# SWITCHCONTROL.net
KiCad netlist of a schematic drawn in EAGLE
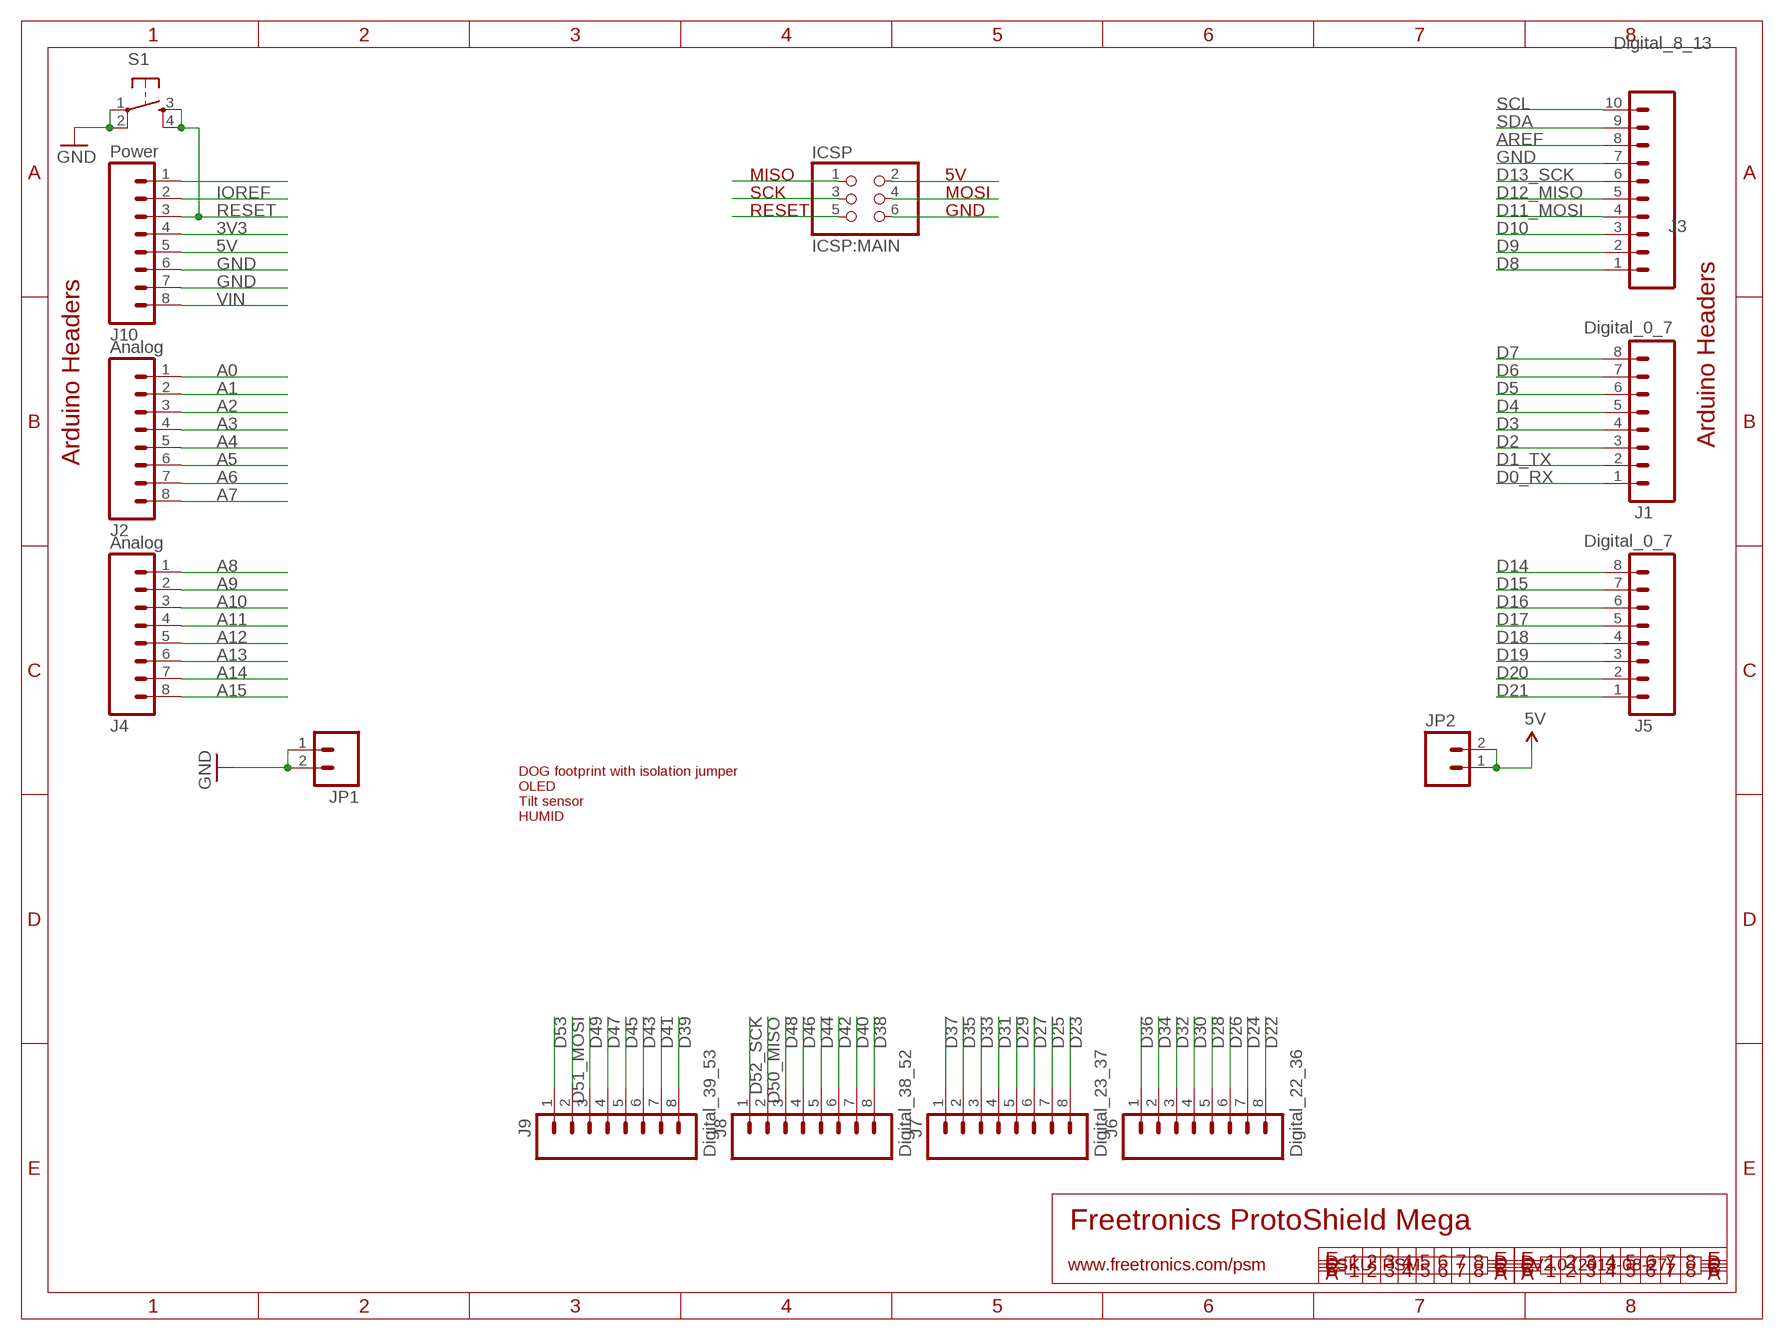
[diagram p0: schematic, sheet 1]
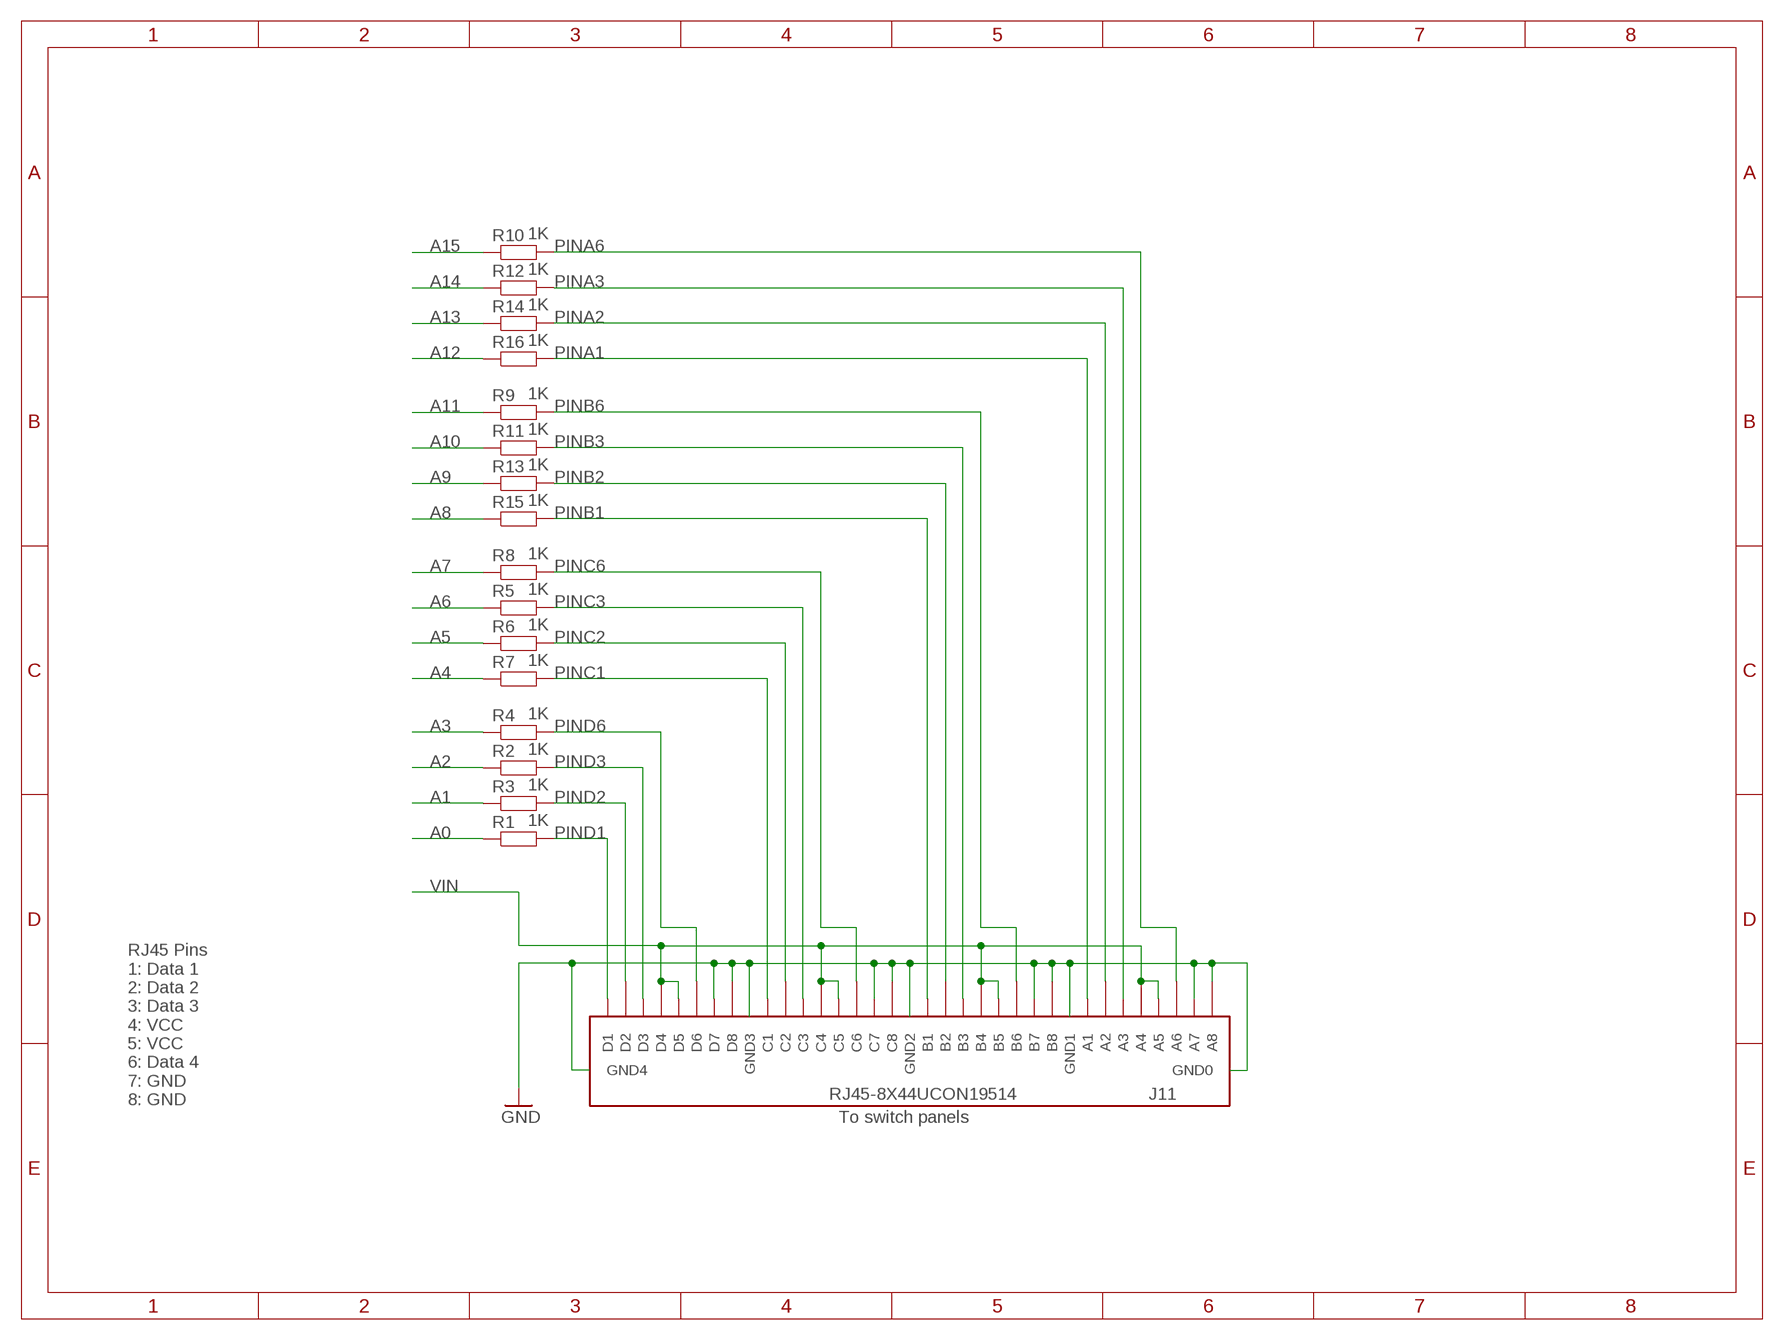
[diagram p1: schematic, sheet 2]
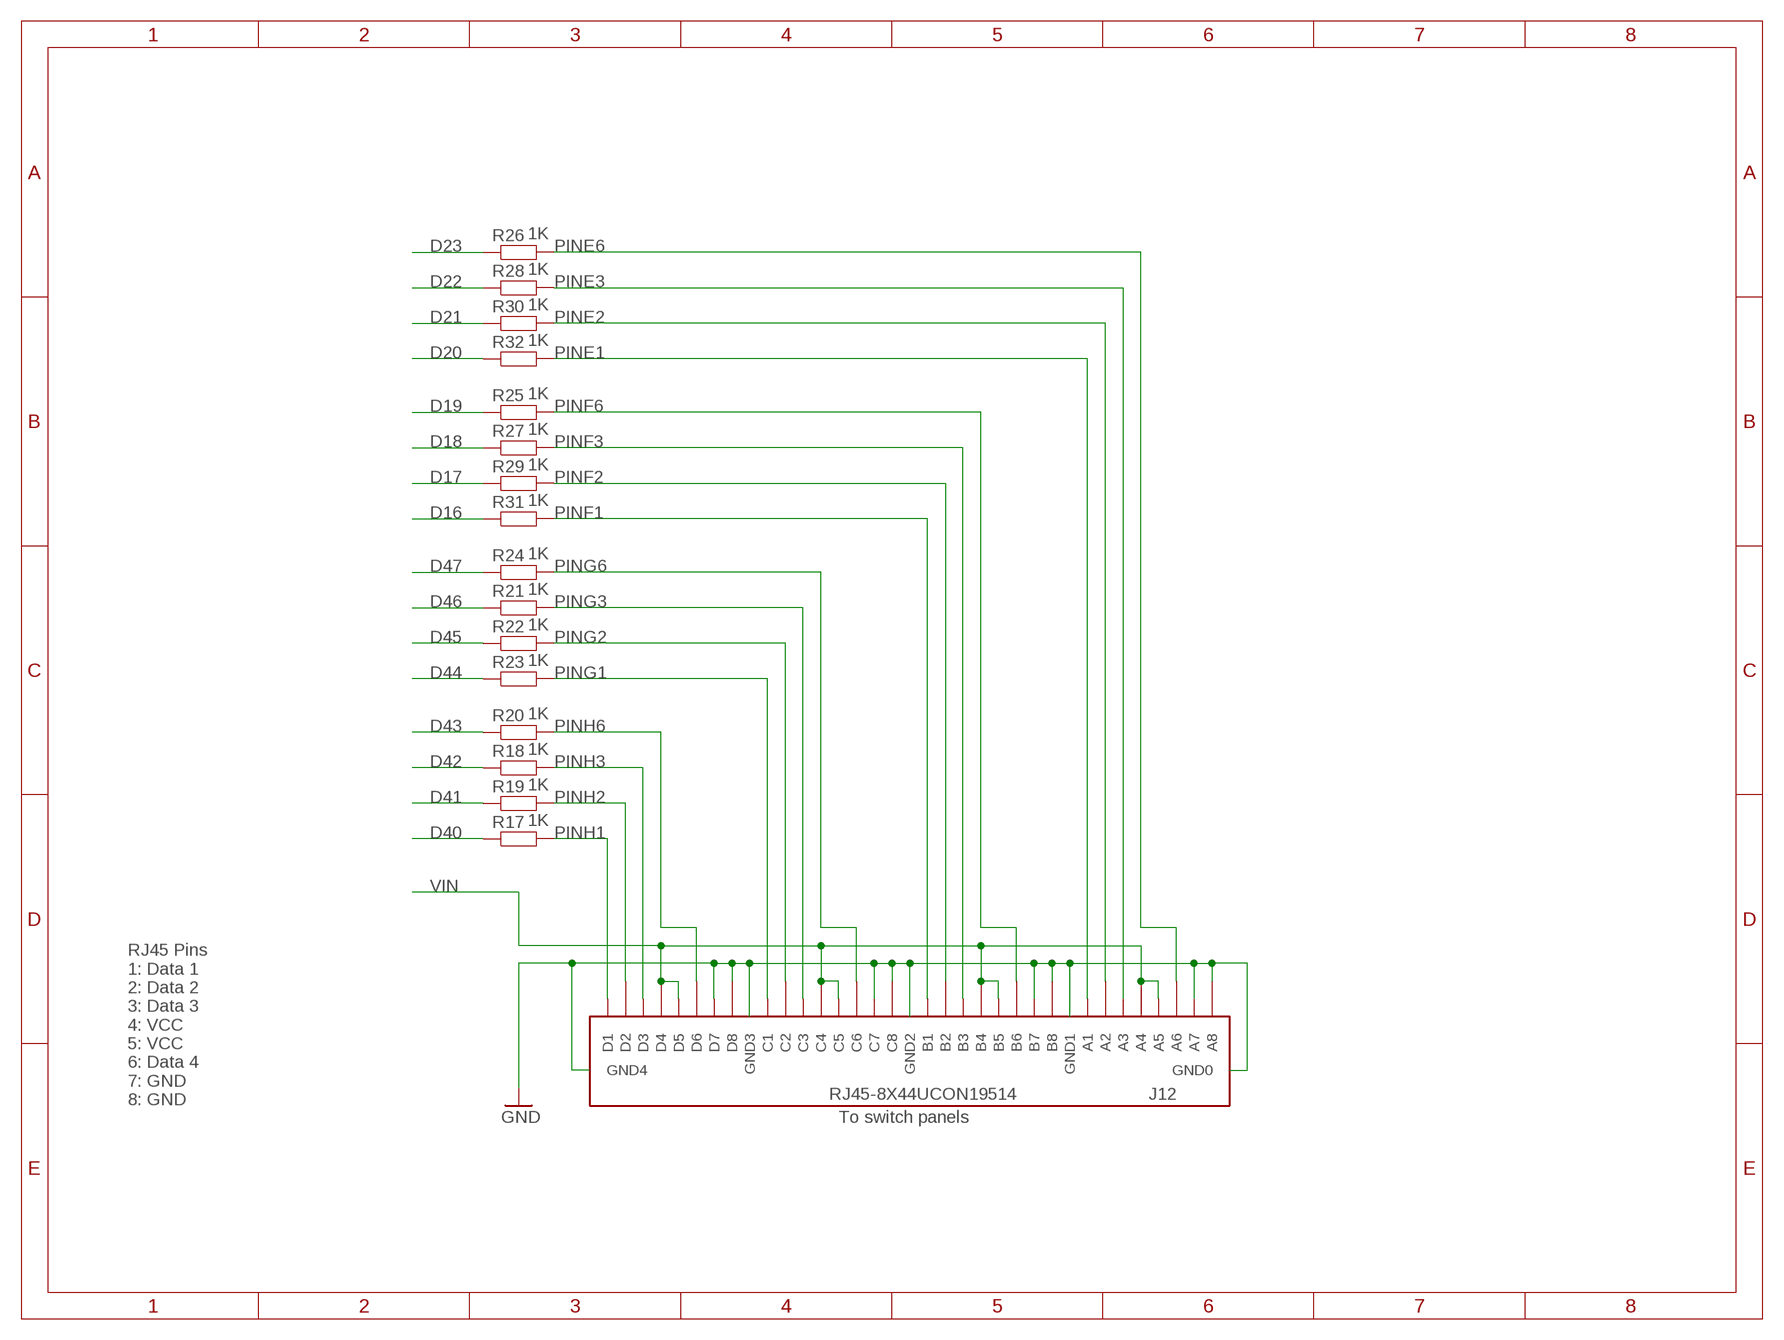
[diagram p2: schematic, sheet 3]
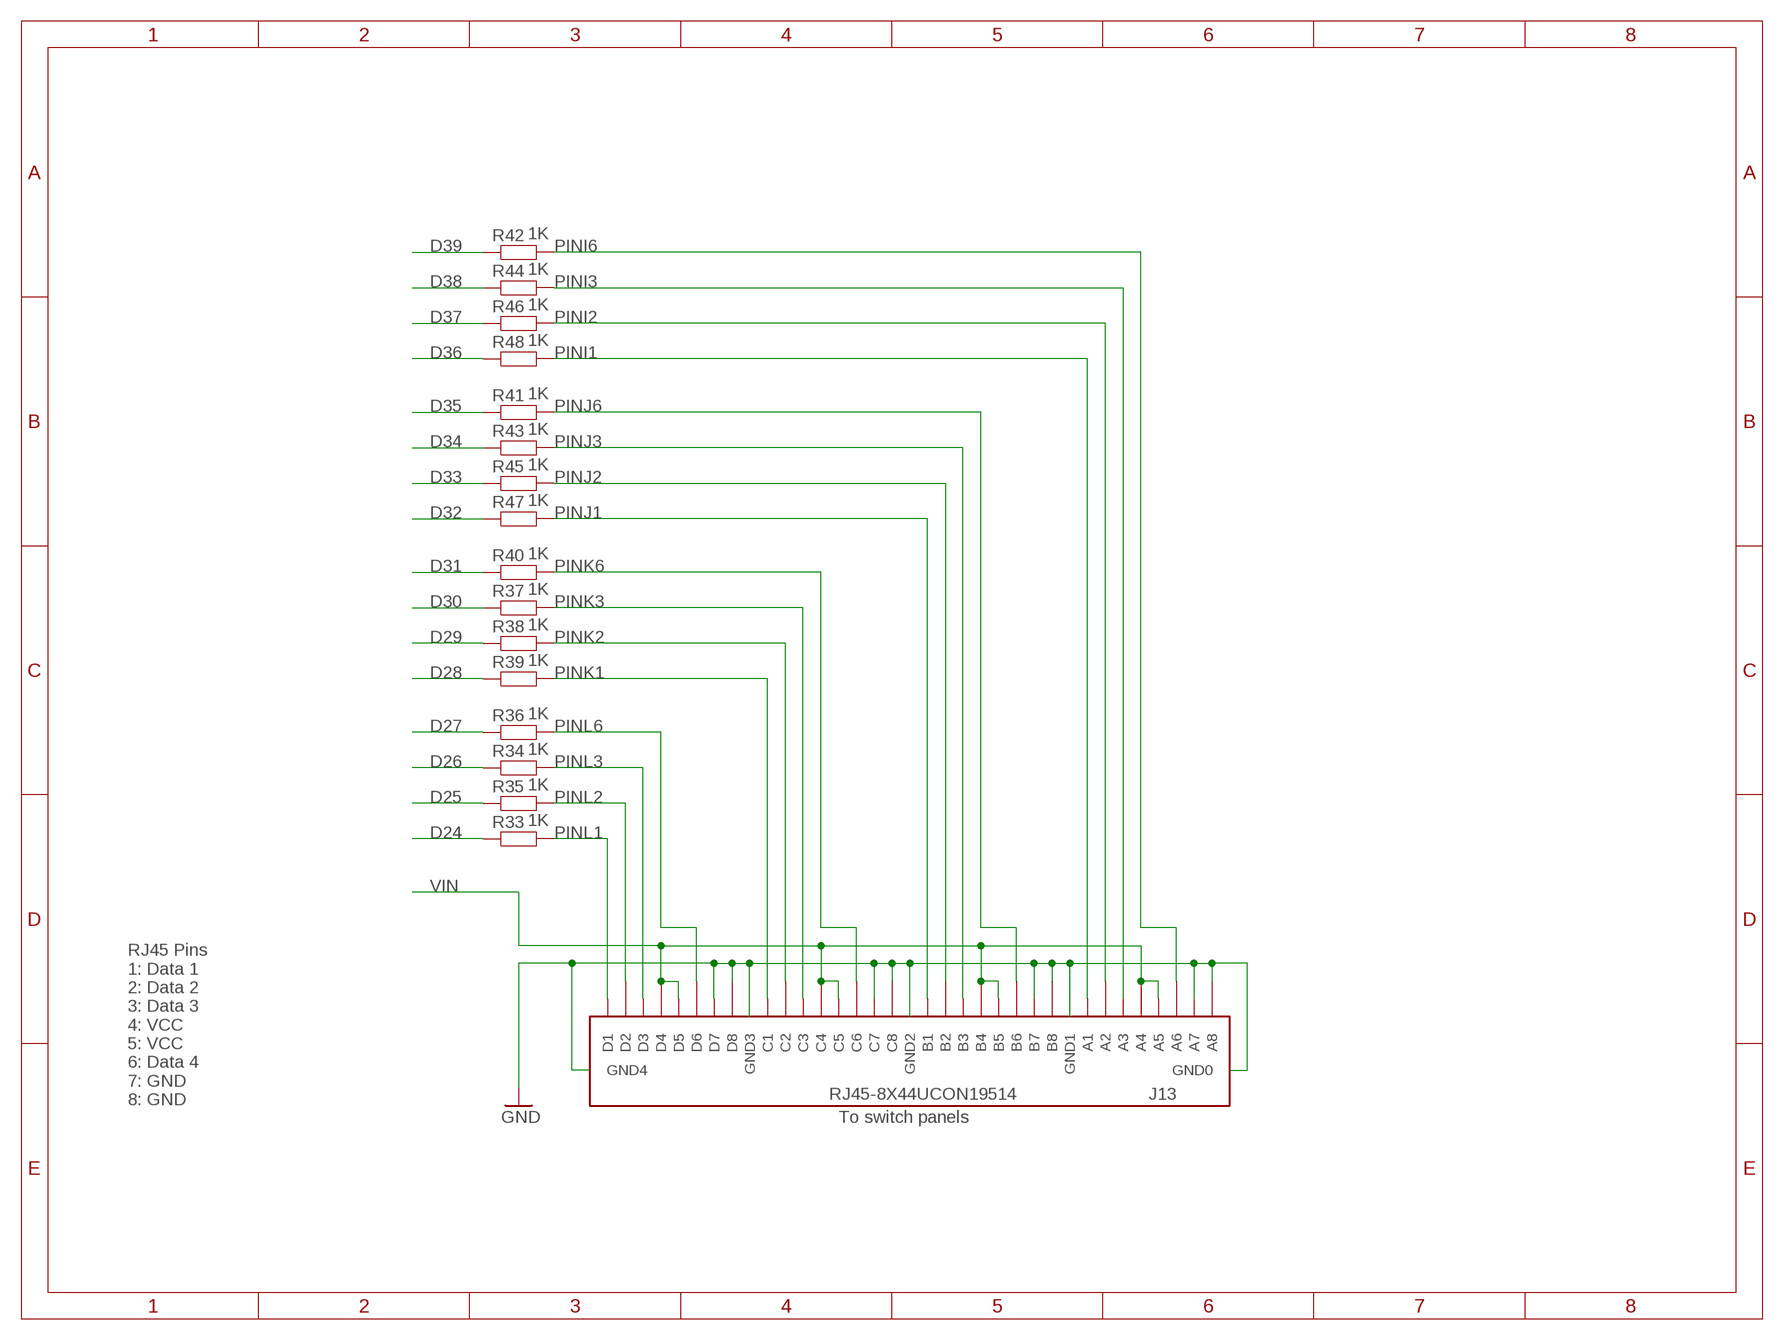
[diagram p3: schematic, sheet 4]

(export (version "E")
  (design (tool "Eeschema 10.0.6"))
  (components
    (comp (ref "J13")
      (value "RJ45-8X44UCON19514")
      (footprint "eagle-import:RJ45-8X4")
      (libsource (lib "eagle-import") (part "RJ45-8X44UCON19514"))
    )
    (comp (ref "R33")
      (value "1K")
      (footprint "eagle-import:0603")
      (libsource (lib "eagle-import") (part "RESISTOR0603"))
    )
    (comp (ref "R34")
      (value "1K")
      (footprint "eagle-import:0603")
      (libsource (lib "eagle-import") (part "RESISTOR0603"))
    )
    (comp (ref "R35")
      (value "1K")
      (footprint "eagle-import:0603")
      (libsource (lib "eagle-import") (part "RESISTOR0603"))
    )
    (comp (ref "R36")
      (value "1K")
      (footprint "eagle-import:0603")
      (libsource (lib "eagle-import") (part "RESISTOR0603"))
    )
    (comp (ref "R37")
      (value "1K")
      (footprint "eagle-import:0603")
      (libsource (lib "eagle-import") (part "RESISTOR0603"))
    )
    (comp (ref "R38")
      (value "1K")
      (footprint "eagle-import:0603")
      (libsource (lib "eagle-import") (part "RESISTOR0603"))
    )
    (comp (ref "R39")
      (value "1K")
      (footprint "eagle-import:0603")
      (libsource (lib "eagle-import") (part "RESISTOR0603"))
    )
    (comp (ref "R40")
      (value "1K")
      (footprint "eagle-import:0603")
      (libsource (lib "eagle-import") (part "RESISTOR0603"))
    )
    (comp (ref "R41")
      (value "1K")
      (footprint "eagle-import:0603")
      (libsource (lib "eagle-import") (part "RESISTOR0603"))
    )
    (comp (ref "R42")
      (value "1K")
      (footprint "eagle-import:0603")
      (libsource (lib "eagle-import") (part "RESISTOR0603"))
    )
    (comp (ref "R43")
      (value "1K")
      (footprint "eagle-import:0603")
      (libsource (lib "eagle-import") (part "RESISTOR0603"))
    )
    (comp (ref "R44")
      (value "1K")
      (footprint "eagle-import:0603")
      (libsource (lib "eagle-import") (part "RESISTOR0603"))
    )
    (comp (ref "R45")
      (value "1K")
      (footprint "eagle-import:0603")
      (libsource (lib "eagle-import") (part "RESISTOR0603"))
    )
    (comp (ref "R46")
      (value "1K")
      (footprint "eagle-import:0603")
      (libsource (lib "eagle-import") (part "RESISTOR0603"))
    )
    (comp (ref "R47")
      (value "1K")
      (footprint "eagle-import:0603")
      (libsource (lib "eagle-import") (part "RESISTOR0603"))
    )
    (comp (ref "R48")
      (value "1K")
      (footprint "eagle-import:0603")
      (libsource (lib "eagle-import") (part "RESISTOR0603"))
    )
    (comp (ref "J12")
      (value "RJ45-8X44UCON19514")
      (footprint "eagle-import:RJ45-8X4")
      (libsource (lib "eagle-import") (part "RJ45-8X44UCON19514"))
    )
    (comp (ref "R17")
      (value "1K")
      (footprint "eagle-import:0603")
      (libsource (lib "eagle-import") (part "RESISTOR0603"))
    )
    (comp (ref "R18")
      (value "1K")
      (footprint "eagle-import:0603")
      (libsource (lib "eagle-import") (part "RESISTOR0603"))
    )
    (comp (ref "R19")
      (value "1K")
      (footprint "eagle-import:0603")
      (libsource (lib "eagle-import") (part "RESISTOR0603"))
    )
    (comp (ref "R20")
      (value "1K")
      (footprint "eagle-import:0603")
      (libsource (lib "eagle-import") (part "RESISTOR0603"))
    )
    (comp (ref "R21")
      (value "1K")
      (footprint "eagle-import:0603")
      (libsource (lib "eagle-import") (part "RESISTOR0603"))
    )
    (comp (ref "R22")
      (value "1K")
      (footprint "eagle-import:0603")
      (libsource (lib "eagle-import") (part "RESISTOR0603"))
    )
    (comp (ref "R23")
      (value "1K")
      (footprint "eagle-import:0603")
      (libsource (lib "eagle-import") (part "RESISTOR0603"))
    )
    (comp (ref "R24")
      (value "1K")
      (footprint "eagle-import:0603")
      (libsource (lib "eagle-import") (part "RESISTOR0603"))
    )
    (comp (ref "R25")
      (value "1K")
      (footprint "eagle-import:0603")
      (libsource (lib "eagle-import") (part "RESISTOR0603"))
    )
    (comp (ref "R26")
      (value "1K")
      (footprint "eagle-import:0603")
      (libsource (lib "eagle-import") (part "RESISTOR0603"))
    )
    (comp (ref "R27")
      (value "1K")
      (footprint "eagle-import:0603")
      (libsource (lib "eagle-import") (part "RESISTOR0603"))
    )
    (comp (ref "R28")
      (value "1K")
      (footprint "eagle-import:0603")
      (libsource (lib "eagle-import") (part "RESISTOR0603"))
    )
    (comp (ref "R29")
      (value "1K")
      (footprint "eagle-import:0603")
      (libsource (lib "eagle-import") (part "RESISTOR0603"))
    )
    (comp (ref "R30")
      (value "1K")
      (footprint "eagle-import:0603")
      (libsource (lib "eagle-import") (part "RESISTOR0603"))
    )
    (comp (ref "R31")
      (value "1K")
      (footprint "eagle-import:0603")
      (libsource (lib "eagle-import") (part "RESISTOR0603"))
    )
    (comp (ref "R32")
      (value "1K")
      (footprint "eagle-import:0603")
      (libsource (lib "eagle-import") (part "RESISTOR0603"))
    )
    (comp (ref "J11")
      (value "RJ45-8X44UCON19514")
      (footprint "eagle-import:RJ45-8X4")
      (libsource (lib "eagle-import") (part "RJ45-8X44UCON19514"))
    )
    (comp (ref "R1")
      (value "1K")
      (footprint "eagle-import:0603")
      (libsource (lib "eagle-import") (part "RESISTOR0603"))
    )
    (comp (ref "R2")
      (value "1K")
      (footprint "eagle-import:0603")
      (libsource (lib "eagle-import") (part "RESISTOR0603"))
    )
    (comp (ref "R3")
      (value "1K")
      (footprint "eagle-import:0603")
      (libsource (lib "eagle-import") (part "RESISTOR0603"))
    )
    (comp (ref "R4")
      (value "1K")
      (footprint "eagle-import:0603")
      (libsource (lib "eagle-import") (part "RESISTOR0603"))
    )
    (comp (ref "R5")
      (value "1K")
      (footprint "eagle-import:0603")
      (libsource (lib "eagle-import") (part "RESISTOR0603"))
    )
    (comp (ref "R6")
      (value "1K")
      (footprint "eagle-import:0603")
      (libsource (lib "eagle-import") (part "RESISTOR0603"))
    )
    (comp (ref "R7")
      (value "1K")
      (footprint "eagle-import:0603")
      (libsource (lib "eagle-import") (part "RESISTOR0603"))
    )
    (comp (ref "R8")
      (value "1K")
      (footprint "eagle-import:0603")
      (libsource (lib "eagle-import") (part "RESISTOR0603"))
    )
    (comp (ref "R9")
      (value "1K")
      (footprint "eagle-import:0603")
      (libsource (lib "eagle-import") (part "RESISTOR0603"))
    )
    (comp (ref "R10")
      (value "1K")
      (footprint "eagle-import:0603")
      (libsource (lib "eagle-import") (part "RESISTOR0603"))
    )
    (comp (ref "R11")
      (value "1K")
      (footprint "eagle-import:0603")
      (libsource (lib "eagle-import") (part "RESISTOR0603"))
    )
    (comp (ref "R12")
      (value "1K")
      (footprint "eagle-import:0603")
      (libsource (lib "eagle-import") (part "RESISTOR0603"))
    )
    (comp (ref "R13")
      (value "1K")
      (footprint "eagle-import:0603")
      (libsource (lib "eagle-import") (part "RESISTOR0603"))
    )
    (comp (ref "R14")
      (value "1K")
      (footprint "eagle-import:0603")
      (libsource (lib "eagle-import") (part "RESISTOR0603"))
    )
    (comp (ref "R15")
      (value "1K")
      (footprint "eagle-import:0603")
      (libsource (lib "eagle-import") (part "RESISTOR0603"))
    )
    (comp (ref "R16")
      (value "1K")
      (footprint "eagle-import:0603")
      (libsource (lib "eagle-import") (part "RESISTOR0603"))
    )
    (comp (ref "ICSP")
      (value "ICSP:MAIN")
      (footprint "eagle-import:2X03")
      (libsource (lib "eagle-import") (part "PINHD-2X3"))
    )
    (comp (ref "J1")
      (value "Digital_0_7")
      (footprint "eagle-import:1X08")
      (libsource (lib "eagle-import") (part "M08"))
    )
    (comp (ref "J2")
      (value "Analog")
      (footprint "eagle-import:1X08")
      (libsource (lib "eagle-import") (part "freetronics-master-v1_M08"))
    )
    (comp (ref "J3")
      (value "Digital_8_13")
      (footprint "eagle-import:1X10")
      (libsource (lib "eagle-import") (part "M100.1"))
    )
    (comp (ref "J4")
      (value "Analog")
      (footprint "eagle-import:1X08")
      (libsource (lib "eagle-import") (part "freetronics-master-v1_M08"))
    )
    (comp (ref "J5")
      (value "Digital_0_7")
      (footprint "eagle-import:1X08")
      (libsource (lib "eagle-import") (part "M08"))
    )
    (comp (ref "J6")
      (value "Digital_22_36")
      (footprint "eagle-import:1X08")
      (libsource (lib "eagle-import") (part "M08"))
    )
    (comp (ref "J7")
      (value "Digital_23_37")
      (footprint "eagle-import:1X08")
      (libsource (lib "eagle-import") (part "M08"))
    )
    (comp (ref "J8")
      (value "Digital_38_52")
      (footprint "eagle-import:1X08")
      (libsource (lib "eagle-import") (part "M08"))
    )
    (comp (ref "J9")
      (value "Digital_39_53")
      (footprint "eagle-import:1X08")
      (libsource (lib "eagle-import") (part "M08"))
    )
    (comp (ref "J10")
      (value "Power")
      (footprint "eagle-import:1X08")
      (libsource (lib "eagle-import") (part "freetronics-master-v1_M08"))
    )
    (comp (ref "JP1")
      (value "M02PTH")
      (footprint "eagle-import:1X02")
      (libsource (lib "eagle-import") (part "M02PTH"))
    )
    (comp (ref "JP2")
      (value "M02PTH")
      (footprint "eagle-import:1X02")
      (libsource (lib "eagle-import") (part "M02PTH"))
    )
    (comp (ref "S1")
      (value "TAC_SWITCHPTH")
      (footprint "eagle-import:TACTILE-PTH")
      (libsource (lib "eagle-import") (part "TAC_SWITCHPTH"))
    )
  )
  (nets
    (net (code "1") (name "3V3") (class "Default")
      (node (ref "J10") (pin "4") (pinfunction "4_4") (pintype "passive"))
    )
    (net (code "2") (name "5V") (class "Default")
      (node (ref "J10") (pin "5") (pinfunction "5_5") (pintype "passive"))
      (node (ref "JP2") (pin "1") (pinfunction "1_1") (pintype "passive"))
      (node (ref "JP2") (pin "2") (pinfunction "2_2") (pintype "passive"))
    )
    (net (code "3") (name "A0") (class "Default")
      (node (ref "J2") (pin "1") (pinfunction "1_1") (pintype "passive"))
      (node (ref "R1") (pin "1") (pinfunction "1_1") (pintype "passive"))
    )
    (net (code "4") (name "A1") (class "Default")
      (node (ref "J2") (pin "2") (pinfunction "2_2") (pintype "passive"))
      (node (ref "R3") (pin "1") (pinfunction "1_1") (pintype "passive"))
    )
    (net (code "5") (name "A2") (class "Default")
      (node (ref "J2") (pin "3") (pinfunction "3_3") (pintype "passive"))
      (node (ref "R2") (pin "1") (pinfunction "1_1") (pintype "passive"))
    )
    (net (code "6") (name "A3") (class "Default")
      (node (ref "J2") (pin "4") (pinfunction "4_4") (pintype "passive"))
      (node (ref "R4") (pin "1") (pinfunction "1_1") (pintype "passive"))
    )
    (net (code "7") (name "A4") (class "Default")
      (node (ref "J2") (pin "5") (pinfunction "5_5") (pintype "passive"))
      (node (ref "R7") (pin "1") (pinfunction "1_1") (pintype "passive"))
    )
    (net (code "8") (name "A5") (class "Default")
      (node (ref "J2") (pin "6") (pinfunction "6_6") (pintype "passive"))
      (node (ref "R6") (pin "1") (pinfunction "1_1") (pintype "passive"))
    )
    (net (code "9") (name "A6") (class "Default")
      (node (ref "J2") (pin "7") (pinfunction "7_7") (pintype "passive"))
      (node (ref "R5") (pin "1") (pinfunction "1_1") (pintype "passive"))
    )
    (net (code "10") (name "A7") (class "Default")
      (node (ref "J2") (pin "8") (pinfunction "8_8") (pintype "passive"))
      (node (ref "R8") (pin "1") (pinfunction "1_1") (pintype "passive"))
    )
    (net (code "11") (name "A8") (class "Default")
      (node (ref "J4") (pin "1") (pinfunction "1_1") (pintype "passive"))
      (node (ref "R15") (pin "1") (pinfunction "1_1") (pintype "passive"))
    )
    (net (code "12") (name "A9") (class "Default")
      (node (ref "J4") (pin "2") (pinfunction "2_2") (pintype "passive"))
      (node (ref "R13") (pin "1") (pinfunction "1_1") (pintype "passive"))
    )
    (net (code "13") (name "A10") (class "Default")
      (node (ref "J4") (pin "3") (pinfunction "3_3") (pintype "passive"))
      (node (ref "R11") (pin "1") (pinfunction "1_1") (pintype "passive"))
    )
    (net (code "14") (name "A11") (class "Default")
      (node (ref "J4") (pin "4") (pinfunction "4_4") (pintype "passive"))
      (node (ref "R9") (pin "1") (pinfunction "1_1") (pintype "passive"))
    )
    (net (code "15") (name "A12") (class "Default")
      (node (ref "J4") (pin "5") (pinfunction "5_5") (pintype "passive"))
      (node (ref "R16") (pin "1") (pinfunction "1_1") (pintype "passive"))
    )
    (net (code "16") (name "A13") (class "Default")
      (node (ref "J4") (pin "6") (pinfunction "6_6") (pintype "passive"))
      (node (ref "R14") (pin "1") (pinfunction "1_1") (pintype "passive"))
    )
    (net (code "17") (name "A14") (class "Default")
      (node (ref "J4") (pin "7") (pinfunction "7_7") (pintype "passive"))
      (node (ref "R12") (pin "1") (pinfunction "1_1") (pintype "passive"))
    )
    (net (code "18") (name "A15") (class "Default")
      (node (ref "J4") (pin "8") (pinfunction "8_8") (pintype "passive"))
      (node (ref "R10") (pin "1") (pinfunction "1_1") (pintype "passive"))
    )
    (net (code "19") (name "AREF") (class "Default")
      (node (ref "J3") (pin "8") (pinfunction "8_8") (pintype "passive"))
    )
    (net (code "20") (name "D0_RX") (class "Default")
      (node (ref "J1") (pin "1") (pinfunction "1_1") (pintype "passive"))
    )
    (net (code "21") (name "D1_TX") (class "Default")
      (node (ref "J1") (pin "2") (pinfunction "2_2") (pintype "passive"))
    )
    (net (code "22") (name "D2") (class "Default")
      (node (ref "J1") (pin "3") (pinfunction "3_3") (pintype "passive"))
    )
    (net (code "23") (name "D3") (class "Default")
      (node (ref "J1") (pin "4") (pinfunction "4_4") (pintype "passive"))
    )
    (net (code "24") (name "D4") (class "Default")
      (node (ref "J1") (pin "5") (pinfunction "5_5") (pintype "passive"))
    )
    (net (code "25") (name "D5") (class "Default")
      (node (ref "J1") (pin "6") (pinfunction "6_6") (pintype "passive"))
    )
    (net (code "26") (name "D6") (class "Default")
      (node (ref "J1") (pin "7") (pinfunction "7_7") (pintype "passive"))
    )
    (net (code "27") (name "D7") (class "Default")
      (node (ref "J1") (pin "8") (pinfunction "8_8") (pintype "passive"))
    )
    (net (code "28") (name "D8") (class "Default")
      (node (ref "J3") (pin "1") (pinfunction "1_1") (pintype "passive"))
    )
    (net (code "29") (name "D9") (class "Default")
      (node (ref "J3") (pin "2") (pinfunction "2_2") (pintype "passive"))
    )
    (net (code "30") (name "D10") (class "Default")
      (node (ref "J3") (pin "3") (pinfunction "3_3") (pintype "passive"))
    )
    (net (code "31") (name "D11_MOSI") (class "Default")
      (node (ref "J3") (pin "4") (pinfunction "4_4") (pintype "passive"))
    )
    (net (code "32") (name "D12_MISO") (class "Default")
      (node (ref "J3") (pin "5") (pinfunction "5_5") (pintype "passive"))
    )
    (net (code "33") (name "D13_SCK") (class "Default")
      (node (ref "J3") (pin "6") (pinfunction "6_6") (pintype "passive"))
    )
    (net (code "34") (name "D14") (class "Default")
      (node (ref "J5") (pin "8") (pinfunction "8_8") (pintype "passive"))
    )
    (net (code "35") (name "D15") (class "Default")
      (node (ref "J5") (pin "7") (pinfunction "7_7") (pintype "passive"))
    )
    (net (code "36") (name "D16") (class "Default")
      (node (ref "J5") (pin "6") (pinfunction "6_6") (pintype "passive"))
      (node (ref "R31") (pin "1") (pinfunction "1_1") (pintype "passive"))
    )
    (net (code "37") (name "D17") (class "Default")
      (node (ref "J5") (pin "5") (pinfunction "5_5") (pintype "passive"))
      (node (ref "R29") (pin "1") (pinfunction "1_1") (pintype "passive"))
    )
    (net (code "38") (name "D18") (class "Default")
      (node (ref "J5") (pin "4") (pinfunction "4_4") (pintype "passive"))
      (node (ref "R27") (pin "1") (pinfunction "1_1") (pintype "passive"))
    )
    (net (code "39") (name "D19") (class "Default")
      (node (ref "J5") (pin "3") (pinfunction "3_3") (pintype "passive"))
      (node (ref "R25") (pin "1") (pinfunction "1_1") (pintype "passive"))
    )
    (net (code "40") (name "D20") (class "Default")
      (node (ref "J5") (pin "2") (pinfunction "2_2") (pintype "passive"))
      (node (ref "R32") (pin "1") (pinfunction "1_1") (pintype "passive"))
    )
    (net (code "41") (name "D21") (class "Default")
      (node (ref "J5") (pin "1") (pinfunction "1_1") (pintype "passive"))
      (node (ref "R30") (pin "1") (pinfunction "1_1") (pintype "passive"))
    )
    (net (code "42") (name "D22") (class "Default")
      (node (ref "J6") (pin "8") (pinfunction "8_8") (pintype "passive"))
      (node (ref "R28") (pin "1") (pinfunction "1_1") (pintype "passive"))
    )
    (net (code "43") (name "D23") (class "Default")
      (node (ref "J7") (pin "8") (pinfunction "8_8") (pintype "passive"))
      (node (ref "R26") (pin "1") (pinfunction "1_1") (pintype "passive"))
    )
    (net (code "44") (name "D24") (class "Default")
      (node (ref "J6") (pin "7") (pinfunction "7_7") (pintype "passive"))
      (node (ref "R33") (pin "1") (pinfunction "1_1") (pintype "passive"))
    )
    (net (code "45") (name "D25") (class "Default")
      (node (ref "J7") (pin "7") (pinfunction "7_7") (pintype "passive"))
      (node (ref "R35") (pin "1") (pinfunction "1_1") (pintype "passive"))
    )
    (net (code "46") (name "D26") (class "Default")
      (node (ref "J6") (pin "6") (pinfunction "6_6") (pintype "passive"))
      (node (ref "R34") (pin "1") (pinfunction "1_1") (pintype "passive"))
    )
    (net (code "47") (name "D27") (class "Default")
      (node (ref "J7") (pin "6") (pinfunction "6_6") (pintype "passive"))
      (node (ref "R36") (pin "1") (pinfunction "1_1") (pintype "passive"))
    )
    (net (code "48") (name "D28") (class "Default")
      (node (ref "J6") (pin "5") (pinfunction "5_5") (pintype "passive"))
      (node (ref "R39") (pin "1") (pinfunction "1_1") (pintype "passive"))
    )
    (net (code "49") (name "D29") (class "Default")
      (node (ref "J7") (pin "5") (pinfunction "5_5") (pintype "passive"))
      (node (ref "R38") (pin "1") (pinfunction "1_1") (pintype "passive"))
    )
    (net (code "50") (name "D30") (class "Default")
      (node (ref "J6") (pin "4") (pinfunction "4_4") (pintype "passive"))
      (node (ref "R37") (pin "1") (pinfunction "1_1") (pintype "passive"))
    )
    (net (code "51") (name "D31") (class "Default")
      (node (ref "J7") (pin "4") (pinfunction "4_4") (pintype "passive"))
      (node (ref "R40") (pin "1") (pinfunction "1_1") (pintype "passive"))
    )
    (net (code "52") (name "D32") (class "Default")
      (node (ref "J6") (pin "3") (pinfunction "3_3") (pintype "passive"))
      (node (ref "R47") (pin "1") (pinfunction "1_1") (pintype "passive"))
    )
    (net (code "53") (name "D33") (class "Default")
      (node (ref "J7") (pin "3") (pinfunction "3_3") (pintype "passive"))
      (node (ref "R45") (pin "1") (pinfunction "1_1") (pintype "passive"))
    )
    (net (code "54") (name "D34") (class "Default")
      (node (ref "J6") (pin "2") (pinfunction "2_2") (pintype "passive"))
      (node (ref "R43") (pin "1") (pinfunction "1_1") (pintype "passive"))
    )
    (net (code "55") (name "D35") (class "Default")
      (node (ref "J7") (pin "2") (pinfunction "2_2") (pintype "passive"))
      (node (ref "R41") (pin "1") (pinfunction "1_1") (pintype "passive"))
    )
    (net (code "56") (name "D36") (class "Default")
      (node (ref "J6") (pin "1") (pinfunction "1_1") (pintype "passive"))
      (node (ref "R48") (pin "1") (pinfunction "1_1") (pintype "passive"))
    )
    (net (code "57") (name "D37") (class "Default")
      (node (ref "J7") (pin "1") (pinfunction "1_1") (pintype "passive"))
      (node (ref "R46") (pin "1") (pinfunction "1_1") (pintype "passive"))
    )
    (net (code "58") (name "D38") (class "Default")
      (node (ref "J8") (pin "8") (pinfunction "8_8") (pintype "passive"))
      (node (ref "R44") (pin "1") (pinfunction "1_1") (pintype "passive"))
    )
    (net (code "59") (name "D39") (class "Default")
      (node (ref "J9") (pin "8") (pinfunction "8_8") (pintype "passive"))
      (node (ref "R42") (pin "1") (pinfunction "1_1") (pintype "passive"))
    )
    (net (code "60") (name "D40") (class "Default")
      (node (ref "J8") (pin "7") (pinfunction "7_7") (pintype "passive"))
      (node (ref "R17") (pin "1") (pinfunction "1_1") (pintype "passive"))
    )
    (net (code "61") (name "D41") (class "Default")
      (node (ref "J9") (pin "7") (pinfunction "7_7") (pintype "passive"))
      (node (ref "R19") (pin "1") (pinfunction "1_1") (pintype "passive"))
    )
    (net (code "62") (name "D42") (class "Default")
      (node (ref "J8") (pin "6") (pinfunction "6_6") (pintype "passive"))
      (node (ref "R18") (pin "1") (pinfunction "1_1") (pintype "passive"))
    )
    (net (code "63") (name "D43") (class "Default")
      (node (ref "J9") (pin "6") (pinfunction "6_6") (pintype "passive"))
      (node (ref "R20") (pin "1") (pinfunction "1_1") (pintype "passive"))
    )
    (net (code "64") (name "D44") (class "Default")
      (node (ref "J8") (pin "5") (pinfunction "5_5") (pintype "passive"))
      (node (ref "R23") (pin "1") (pinfunction "1_1") (pintype "passive"))
    )
    (net (code "65") (name "D45") (class "Default")
      (node (ref "J9") (pin "5") (pinfunction "5_5") (pintype "passive"))
      (node (ref "R22") (pin "1") (pinfunction "1_1") (pintype "passive"))
    )
    (net (code "66") (name "D46") (class "Default")
      (node (ref "J8") (pin "4") (pinfunction "4_4") (pintype "passive"))
      (node (ref "R21") (pin "1") (pinfunction "1_1") (pintype "passive"))
    )
    (net (code "67") (name "D47") (class "Default")
      (node (ref "J9") (pin "4") (pinfunction "4_4") (pintype "passive"))
      (node (ref "R24") (pin "1") (pinfunction "1_1") (pintype "passive"))
    )
    (net (code "68") (name "D48") (class "Default")
      (node (ref "J8") (pin "3") (pinfunction "3_3") (pintype "passive"))
    )
    (net (code "69") (name "D49") (class "Default")
      (node (ref "J9") (pin "3") (pinfunction "3_3") (pintype "passive"))
    )
    (net (code "70") (name "D50_MISO") (class "Default")
      (node (ref "J8") (pin "2") (pinfunction "2_2") (pintype "passive"))
    )
    (net (code "71") (name "D51_MOSI") (class "Default")
      (node (ref "J9") (pin "2") (pinfunction "2_2") (pintype "passive"))
    )
    (net (code "72") (name "D52_SCK") (class "Default")
      (node (ref "J8") (pin "1") (pinfunction "1_1") (pintype "passive"))
    )
    (net (code "73") (name "D53") (class "Default")
      (node (ref "J9") (pin "1") (pinfunction "1_1") (pintype "passive"))
    )
    (net (code "74") (name "GND") (class "Default")
      (node (ref "J10") (pin "6") (pinfunction "6_6") (pintype "passive"))
      (node (ref "J10") (pin "7") (pinfunction "7_7") (pintype "passive"))
      (node (ref "J11") (pin "A7") (pinfunction "A7_A7") (pintype "bidirectional"))
      (node (ref "J11") (pin "A8") (pinfunction "A8_A8") (pintype "bidirectional"))
      (node (ref "J11") (pin "B7") (pinfunction "B7_B7") (pintype "bidirectional"))
      (node (ref "J11") (pin "B8") (pinfunction "B8_B8") (pintype "bidirectional"))
      (node (ref "J11") (pin "C7") (pinfunction "C7_C7") (pintype "bidirectional"))
      (node (ref "J11") (pin "C8") (pinfunction "C8_C8") (pintype "bidirectional"))
      (node (ref "J11") (pin "D7") (pinfunction "D7_D7") (pintype "bidirectional"))
      (node (ref "J11") (pin "D8") (pinfunction "D8_D8") (pintype "bidirectional"))
      (node (ref "J11") (pin "GND0") (pinfunction "GND0_GND0") (pintype "power_in"))
      (node (ref "J11") (pin "GND1") (pinfunction "GND1_GND1") (pintype "power_in"))
      (node (ref "J11") (pin "GND2") (pinfunction "GND2_GND2") (pintype "power_in"))
      (node (ref "J11") (pin "GND3") (pinfunction "GND3_GND3") (pintype "power_in"))
      (node (ref "J11") (pin "GND4") (pinfunction "GND4_GND4") (pintype "power_in"))
      (node (ref "J12") (pin "A7") (pinfunction "A7_A7") (pintype "bidirectional"))
      (node (ref "J12") (pin "A8") (pinfunction "A8_A8") (pintype "bidirectional"))
      (node (ref "J12") (pin "B7") (pinfunction "B7_B7") (pintype "bidirectional"))
      (node (ref "J12") (pin "B8") (pinfunction "B8_B8") (pintype "bidirectional"))
      (node (ref "J12") (pin "C7") (pinfunction "C7_C7") (pintype "bidirectional"))
      (node (ref "J12") (pin "C8") (pinfunction "C8_C8") (pintype "bidirectional"))
      (node (ref "J12") (pin "D7") (pinfunction "D7_D7") (pintype "bidirectional"))
      (node (ref "J12") (pin "D8") (pinfunction "D8_D8") (pintype "bidirectional"))
      (node (ref "J12") (pin "GND0") (pinfunction "GND0_GND0") (pintype "power_in"))
      (node (ref "J12") (pin "GND1") (pinfunction "GND1_GND1") (pintype "power_in"))
      (node (ref "J12") (pin "GND2") (pinfunction "GND2_GND2") (pintype "power_in"))
      (node (ref "J12") (pin "GND3") (pinfunction "GND3_GND3") (pintype "power_in"))
      (node (ref "J12") (pin "GND4") (pinfunction "GND4_GND4") (pintype "power_in"))
      (node (ref "J13") (pin "A7") (pinfunction "A7_A7") (pintype "bidirectional"))
      (node (ref "J13") (pin "A8") (pinfunction "A8_A8") (pintype "bidirectional"))
      (node (ref "J13") (pin "B7") (pinfunction "B7_B7") (pintype "bidirectional"))
      (node (ref "J13") (pin "B8") (pinfunction "B8_B8") (pintype "bidirectional"))
      (node (ref "J13") (pin "C7") (pinfunction "C7_C7") (pintype "bidirectional"))
      (node (ref "J13") (pin "C8") (pinfunction "C8_C8") (pintype "bidirectional"))
      (node (ref "J13") (pin "D7") (pinfunction "D7_D7") (pintype "bidirectional"))
      (node (ref "J13") (pin "D8") (pinfunction "D8_D8") (pintype "bidirectional"))
      (node (ref "J13") (pin "GND0") (pinfunction "GND0_GND0") (pintype "power_in"))
      (node (ref "J13") (pin "GND1") (pinfunction "GND1_GND1") (pintype "power_in"))
      (node (ref "J13") (pin "GND2") (pinfunction "GND2_GND2") (pintype "power_in"))
      (node (ref "J13") (pin "GND3") (pinfunction "GND3_GND3") (pintype "power_in"))
      (node (ref "J13") (pin "GND4") (pinfunction "GND4_GND4") (pintype "power_in"))
      (node (ref "J3") (pin "7") (pinfunction "7_7") (pintype "passive"))
      (node (ref "JP1") (pin "1") (pinfunction "1_1") (pintype "passive"))
      (node (ref "JP1") (pin "2") (pinfunction "2_2") (pintype "passive"))
      (node (ref "S1") (pin "1") (pinfunction "1_1") (pintype "passive"))
      (node (ref "S1") (pin "2") (pinfunction "2_2") (pintype "passive"))
    )
    (net (code "75") (name "IOREF") (class "Default")
      (node (ref "J10") (pin "2") (pinfunction "2_2") (pintype "passive"))
    )
    (net (code "76") (name "PINA1") (class "Default")
      (node (ref "J11") (pin "A1") (pinfunction "A1_A1") (pintype "bidirectional"))
      (node (ref "R16") (pin "2") (pinfunction "2_2") (pintype "passive"))
    )
    (net (code "77") (name "PINA2") (class "Default")
      (node (ref "J11") (pin "A2") (pinfunction "A2_A2") (pintype "bidirectional"))
      (node (ref "R14") (pin "2") (pinfunction "2_2") (pintype "passive"))
    )
    (net (code "78") (name "PINA3") (class "Default")
      (node (ref "J11") (pin "A3") (pinfunction "A3_A3") (pintype "bidirectional"))
      (node (ref "R12") (pin "2") (pinfunction "2_2") (pintype "passive"))
    )
    (net (code "79") (name "PINA6") (class "Default")
      (node (ref "J11") (pin "A6") (pinfunction "A6_A6") (pintype "bidirectional"))
      (node (ref "R10") (pin "2") (pinfunction "2_2") (pintype "passive"))
    )
    (net (code "80") (name "PINB1") (class "Default")
      (node (ref "J11") (pin "B1") (pinfunction "B1_B1") (pintype "bidirectional"))
      (node (ref "R15") (pin "2") (pinfunction "2_2") (pintype "passive"))
    )
    (net (code "81") (name "PINB2") (class "Default")
      (node (ref "J11") (pin "B2") (pinfunction "B2_B2") (pintype "bidirectional"))
      (node (ref "R13") (pin "2") (pinfunction "2_2") (pintype "passive"))
    )
    (net (code "82") (name "PINB3") (class "Default")
      (node (ref "J11") (pin "B3") (pinfunction "B3_B3") (pintype "bidirectional"))
      (node (ref "R11") (pin "2") (pinfunction "2_2") (pintype "passive"))
    )
    (net (code "83") (name "PINB6") (class "Default")
      (node (ref "J11") (pin "B6") (pinfunction "B6_B6") (pintype "bidirectional"))
      (node (ref "R9") (pin "2") (pinfunction "2_2") (pintype "passive"))
    )
    (net (code "84") (name "PINC1") (class "Default")
      (node (ref "J11") (pin "C1") (pinfunction "C1_C1") (pintype "bidirectional"))
      (node (ref "R7") (pin "2") (pinfunction "2_2") (pintype "passive"))
    )
    (net (code "85") (name "PINC2") (class "Default")
      (node (ref "J11") (pin "C2") (pinfunction "C2_C2") (pintype "bidirectional"))
      (node (ref "R6") (pin "2") (pinfunction "2_2") (pintype "passive"))
    )
    (net (code "86") (name "PINC3") (class "Default")
      (node (ref "J11") (pin "C3") (pinfunction "C3_C3") (pintype "bidirectional"))
      (node (ref "R5") (pin "2") (pinfunction "2_2") (pintype "passive"))
    )
    (net (code "87") (name "PINC6") (class "Default")
      (node (ref "J11") (pin "C6") (pinfunction "C6_C6") (pintype "bidirectional"))
      (node (ref "R8") (pin "2") (pinfunction "2_2") (pintype "passive"))
    )
    (net (code "88") (name "PIND1") (class "Default")
      (node (ref "J11") (pin "D1") (pinfunction "D1_D1") (pintype "bidirectional"))
      (node (ref "R1") (pin "2") (pinfunction "2_2") (pintype "passive"))
    )
    (net (code "89") (name "PIND2") (class "Default")
      (node (ref "J11") (pin "D2") (pinfunction "D2_D2") (pintype "bidirectional"))
      (node (ref "R3") (pin "2") (pinfunction "2_2") (pintype "passive"))
    )
    (net (code "90") (name "PIND3") (class "Default")
      (node (ref "J11") (pin "D3") (pinfunction "D3_D3") (pintype "bidirectional"))
      (node (ref "R2") (pin "2") (pinfunction "2_2") (pintype "passive"))
    )
    (net (code "91") (name "PIND6") (class "Default")
      (node (ref "J11") (pin "D6") (pinfunction "D6_D6") (pintype "bidirectional"))
      (node (ref "R4") (pin "2") (pinfunction "2_2") (pintype "passive"))
    )
    (net (code "92") (name "PINE1") (class "Default")
      (node (ref "J12") (pin "A1") (pinfunction "A1_A1") (pintype "bidirectional"))
      (node (ref "R32") (pin "2") (pinfunction "2_2") (pintype "passive"))
    )
    (net (code "93") (name "PINE2") (class "Default")
      (node (ref "J12") (pin "A2") (pinfunction "A2_A2") (pintype "bidirectional"))
      (node (ref "R30") (pin "2") (pinfunction "2_2") (pintype "passive"))
    )
    (net (code "94") (name "PINE3") (class "Default")
      (node (ref "J12") (pin "A3") (pinfunction "A3_A3") (pintype "bidirectional"))
      (node (ref "R28") (pin "2") (pinfunction "2_2") (pintype "passive"))
    )
    (net (code "95") (name "PINE6") (class "Default")
      (node (ref "J12") (pin "A6") (pinfunction "A6_A6") (pintype "bidirectional"))
      (node (ref "R26") (pin "2") (pinfunction "2_2") (pintype "passive"))
    )
    (net (code "96") (name "PINF1") (class "Default")
      (node (ref "J12") (pin "B1") (pinfunction "B1_B1") (pintype "bidirectional"))
      (node (ref "R31") (pin "2") (pinfunction "2_2") (pintype "passive"))
    )
    (net (code "97") (name "PINF2") (class "Default")
      (node (ref "J12") (pin "B2") (pinfunction "B2_B2") (pintype "bidirectional"))
      (node (ref "R29") (pin "2") (pinfunction "2_2") (pintype "passive"))
    )
    (net (code "98") (name "PINF3") (class "Default")
      (node (ref "J12") (pin "B3") (pinfunction "B3_B3") (pintype "bidirectional"))
      (node (ref "R27") (pin "2") (pinfunction "2_2") (pintype "passive"))
    )
    (net (code "99") (name "PINF6") (class "Default")
      (node (ref "J12") (pin "B6") (pinfunction "B6_B6") (pintype "bidirectional"))
      (node (ref "R25") (pin "2") (pinfunction "2_2") (pintype "passive"))
    )
    (net (code "100") (name "PING1") (class "Default")
      (node (ref "J12") (pin "C1") (pinfunction "C1_C1") (pintype "bidirectional"))
      (node (ref "R23") (pin "2") (pinfunction "2_2") (pintype "passive"))
    )
    (net (code "101") (name "PING2") (class "Default")
      (node (ref "J12") (pin "C2") (pinfunction "C2_C2") (pintype "bidirectional"))
      (node (ref "R22") (pin "2") (pinfunction "2_2") (pintype "passive"))
    )
    (net (code "102") (name "PING3") (class "Default")
      (node (ref "J12") (pin "C3") (pinfunction "C3_C3") (pintype "bidirectional"))
      (node (ref "R21") (pin "2") (pinfunction "2_2") (pintype "passive"))
    )
    (net (code "103") (name "PING6") (class "Default")
      (node (ref "J12") (pin "C6") (pinfunction "C6_C6") (pintype "bidirectional"))
      (node (ref "R24") (pin "2") (pinfunction "2_2") (pintype "passive"))
    )
    (net (code "104") (name "PINH1") (class "Default")
      (node (ref "J12") (pin "D1") (pinfunction "D1_D1") (pintype "bidirectional"))
      (node (ref "R17") (pin "2") (pinfunction "2_2") (pintype "passive"))
    )
    (net (code "105") (name "PINH2") (class "Default")
      (node (ref "J12") (pin "D2") (pinfunction "D2_D2") (pintype "bidirectional"))
      (node (ref "R19") (pin "2") (pinfunction "2_2") (pintype "passive"))
    )
    (net (code "106") (name "PINH3") (class "Default")
      (node (ref "J12") (pin "D3") (pinfunction "D3_D3") (pintype "bidirectional"))
      (node (ref "R18") (pin "2") (pinfunction "2_2") (pintype "passive"))
    )
    (net (code "107") (name "PINH6") (class "Default")
      (node (ref "J12") (pin "D6") (pinfunction "D6_D6") (pintype "bidirectional"))
      (node (ref "R20") (pin "2") (pinfunction "2_2") (pintype "passive"))
    )
    (net (code "108") (name "PINI1") (class "Default")
      (node (ref "J13") (pin "A1") (pinfunction "A1_A1") (pintype "bidirectional"))
      (node (ref "R48") (pin "2") (pinfunction "2_2") (pintype "passive"))
    )
    (net (code "109") (name "PINI2") (class "Default")
      (node (ref "J13") (pin "A2") (pinfunction "A2_A2") (pintype "bidirectional"))
      (node (ref "R46") (pin "2") (pinfunction "2_2") (pintype "passive"))
    )
    (net (code "110") (name "PINI3") (class "Default")
      (node (ref "J13") (pin "A3") (pinfunction "A3_A3") (pintype "bidirectional"))
      (node (ref "R44") (pin "2") (pinfunction "2_2") (pintype "passive"))
    )
    (net (code "111") (name "PINI6") (class "Default")
      (node (ref "J13") (pin "A6") (pinfunction "A6_A6") (pintype "bidirectional"))
      (node (ref "R42") (pin "2") (pinfunction "2_2") (pintype "passive"))
    )
    (net (code "112") (name "PINJ1") (class "Default")
      (node (ref "J13") (pin "B1") (pinfunction "B1_B1") (pintype "bidirectional"))
      (node (ref "R47") (pin "2") (pinfunction "2_2") (pintype "passive"))
    )
    (net (code "113") (name "PINJ2") (class "Default")
      (node (ref "J13") (pin "B2") (pinfunction "B2_B2") (pintype "bidirectional"))
      (node (ref "R45") (pin "2") (pinfunction "2_2") (pintype "passive"))
    )
    (net (code "114") (name "PINJ3") (class "Default")
      (node (ref "J13") (pin "B3") (pinfunction "B3_B3") (pintype "bidirectional"))
      (node (ref "R43") (pin "2") (pinfunction "2_2") (pintype "passive"))
    )
    (net (code "115") (name "PINJ6") (class "Default")
      (node (ref "J13") (pin "B6") (pinfunction "B6_B6") (pintype "bidirectional"))
      (node (ref "R41") (pin "2") (pinfunction "2_2") (pintype "passive"))
    )
    (net (code "116") (name "PINK1") (class "Default")
      (node (ref "J13") (pin "C1") (pinfunction "C1_C1") (pintype "bidirectional"))
      (node (ref "R39") (pin "2") (pinfunction "2_2") (pintype "passive"))
    )
    (net (code "117") (name "PINK2") (class "Default")
      (node (ref "J13") (pin "C2") (pinfunction "C2_C2") (pintype "bidirectional"))
      (node (ref "R38") (pin "2") (pinfunction "2_2") (pintype "passive"))
    )
    (net (code "118") (name "PINK3") (class "Default")
      (node (ref "J13") (pin "C3") (pinfunction "C3_C3") (pintype "bidirectional"))
      (node (ref "R37") (pin "2") (pinfunction "2_2") (pintype "passive"))
    )
    (net (code "119") (name "PINK6") (class "Default")
      (node (ref "J13") (pin "C6") (pinfunction "C6_C6") (pintype "bidirectional"))
      (node (ref "R40") (pin "2") (pinfunction "2_2") (pintype "passive"))
    )
    (net (code "120") (name "PINL1") (class "Default")
      (node (ref "J13") (pin "D1") (pinfunction "D1_D1") (pintype "bidirectional"))
      (node (ref "R33") (pin "2") (pinfunction "2_2") (pintype "passive"))
    )
    (net (code "121") (name "PINL2") (class "Default")
      (node (ref "J13") (pin "D2") (pinfunction "D2_D2") (pintype "bidirectional"))
      (node (ref "R35") (pin "2") (pinfunction "2_2") (pintype "passive"))
    )
    (net (code "122") (name "PINL3") (class "Default")
      (node (ref "J13") (pin "D3") (pinfunction "D3_D3") (pintype "bidirectional"))
      (node (ref "R34") (pin "2") (pinfunction "2_2") (pintype "passive"))
    )
    (net (code "123") (name "PINL6") (class "Default")
      (node (ref "J13") (pin "D6") (pinfunction "D6_D6") (pintype "bidirectional"))
      (node (ref "R36") (pin "2") (pinfunction "2_2") (pintype "passive"))
    )
    (net (code "124") (name "RESET") (class "Default")
      (node (ref "J10") (pin "3") (pinfunction "3_3") (pintype "passive"))
      (node (ref "S1") (pin "3") (pinfunction "3_3") (pintype "passive"))
      (node (ref "S1") (pin "4") (pinfunction "4_4") (pintype "passive"))
    )
    (net (code "125") (name "SCL") (class "Default")
      (node (ref "J3") (pin "10") (pinfunction "10_10") (pintype "passive"))
    )
    (net (code "126") (name "SDA") (class "Default")
      (node (ref "J3") (pin "9") (pinfunction "9_9") (pintype "passive"))
    )
    (net (code "127") (name "VIN") (class "Default")
      (node (ref "J10") (pin "8") (pinfunction "8_8") (pintype "passive"))
      (node (ref "J11") (pin "A4") (pinfunction "A4_A4") (pintype "bidirectional"))
      (node (ref "J11") (pin "A5") (pinfunction "A5_A5") (pintype "bidirectional"))
      (node (ref "J11") (pin "B4") (pinfunction "B4_B4") (pintype "bidirectional"))
      (node (ref "J11") (pin "B5") (pinfunction "B5_B5") (pintype "bidirectional"))
      (node (ref "J11") (pin "C4") (pinfunction "C4_C4") (pintype "bidirectional"))
      (node (ref "J11") (pin "C5") (pinfunction "C5_C5") (pintype "bidirectional"))
      (node (ref "J11") (pin "D4") (pinfunction "D4_D4") (pintype "bidirectional"))
      (node (ref "J11") (pin "D5") (pinfunction "D5_D5") (pintype "bidirectional"))
      (node (ref "J12") (pin "A4") (pinfunction "A4_A4") (pintype "bidirectional"))
      (node (ref "J12") (pin "A5") (pinfunction "A5_A5") (pintype "bidirectional"))
      (node (ref "J12") (pin "B4") (pinfunction "B4_B4") (pintype "bidirectional"))
      (node (ref "J12") (pin "B5") (pinfunction "B5_B5") (pintype "bidirectional"))
      (node (ref "J12") (pin "C4") (pinfunction "C4_C4") (pintype "bidirectional"))
      (node (ref "J12") (pin "C5") (pinfunction "C5_C5") (pintype "bidirectional"))
      (node (ref "J12") (pin "D4") (pinfunction "D4_D4") (pintype "bidirectional"))
      (node (ref "J12") (pin "D5") (pinfunction "D5_D5") (pintype "bidirectional"))
      (node (ref "J13") (pin "A4") (pinfunction "A4_A4") (pintype "bidirectional"))
      (node (ref "J13") (pin "A5") (pinfunction "A5_A5") (pintype "bidirectional"))
      (node (ref "J13") (pin "B4") (pinfunction "B4_B4") (pintype "bidirectional"))
      (node (ref "J13") (pin "B5") (pinfunction "B5_B5") (pintype "bidirectional"))
      (node (ref "J13") (pin "C4") (pinfunction "C4_C4") (pintype "bidirectional"))
      (node (ref "J13") (pin "C5") (pinfunction "C5_C5") (pintype "bidirectional"))
      (node (ref "J13") (pin "D4") (pinfunction "D4_D4") (pintype "bidirectional"))
      (node (ref "J13") (pin "D5") (pinfunction "D5_D5") (pintype "bidirectional"))
    )
    (net (code "128") (name "unconnected-(ICSP-Pad1)") (class "Default")
      (node (ref "ICSP") (pin "1") (pinfunction "1_1") (pintype "passive"))
    )
    (net (code "129") (name "unconnected-(ICSP-Pad2)") (class "Default")
      (node (ref "ICSP") (pin "2") (pinfunction "2_2") (pintype "passive"))
    )
    (net (code "130") (name "unconnected-(ICSP-Pad3)") (class "Default")
      (node (ref "ICSP") (pin "3") (pinfunction "3_3") (pintype "passive"))
    )
    (net (code "131") (name "unconnected-(ICSP-Pad4)") (class "Default")
      (node (ref "ICSP") (pin "4") (pinfunction "4_4") (pintype "passive"))
    )
    (net (code "132") (name "unconnected-(ICSP-Pad5)") (class "Default")
      (node (ref "ICSP") (pin "5") (pinfunction "5_5") (pintype "passive"))
    )
    (net (code "133") (name "unconnected-(ICSP-Pad6)") (class "Default")
      (node (ref "ICSP") (pin "6") (pinfunction "6_6") (pintype "passive"))
    )
    (net (code "134") (name "unconnected-(J10-Pad1)") (class "Default")
      (node (ref "J10") (pin "1") (pinfunction "1_1") (pintype "passive"))
    )
  )
)
